# mcu_atmega.net
KiCad netlist of a schematic drawn in Altium Designer
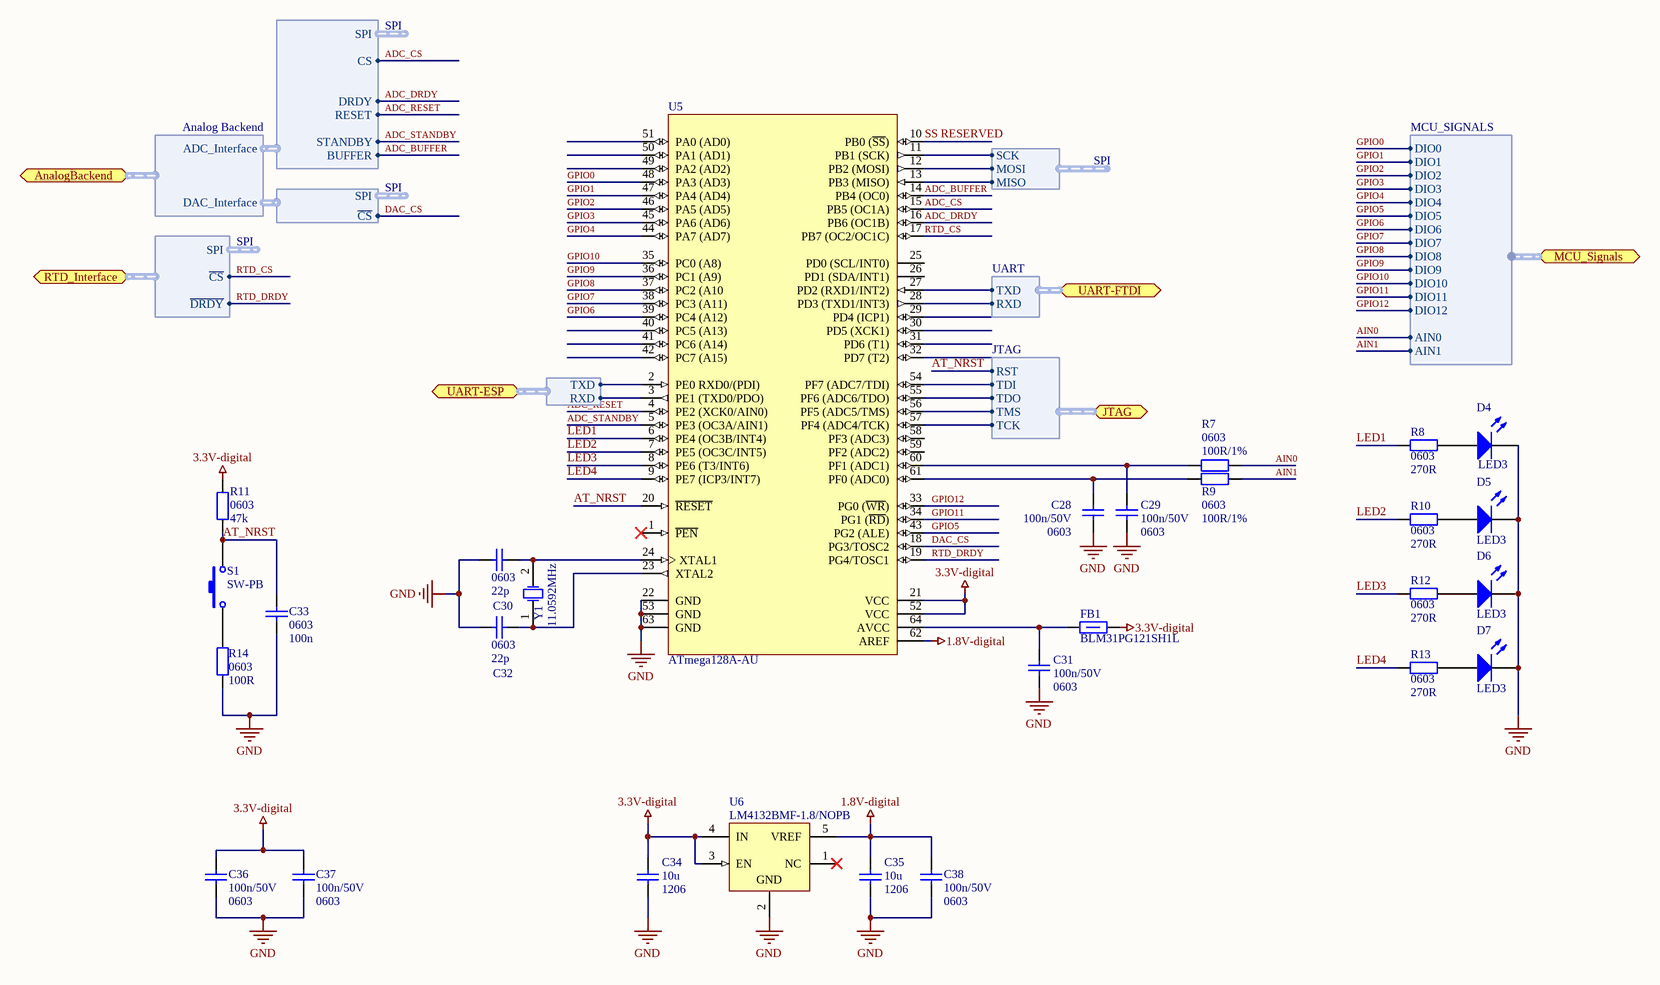
[diagram p0: mcu_atmega.SchDoc]

(export (version "E")
  (design (tool "Eeschema 10.0.6"))
  (components
    (comp (ref "C28")
      (value "100n/50V")
      (footprint "SMD_Capacitor_0603")
      (description "Ceramic Cap Kemet COTS 100n/50V X7R 0603")
      (fields
        (field (name "MANUFACTURER") "Kemet")
        (field (name "MANUFACTURERPARTNUMBER") "C0603T104K5RALTU")
        (field (name "PACKAGE") "0603")
      )
      (libsource (lib "capacitors") (part "Cer_C0603T104K5RALTU"))
    )
    (comp (ref "C29")
      (value "100n/50V")
      (footprint "SMD_Capacitor_0603")
      (description "Ceramic Cap Kemet COTS 100n/50V X7R 0603")
      (fields
        (field (name "MANUFACTURER") "Kemet")
        (field (name "MANUFACTURERPARTNUMBER") "C0603T104K5RALTU")
        (field (name "PACKAGE") "0603")
      )
      (libsource (lib "capacitors") (part "Cer_C0603T104K5RALTU"))
    )
    (comp (ref "C30")
      (value "0603")
      (footprint "SMD_Capacitor_0603")
      (description "Capacitor")
      (fields (field (name "ALTIUM_VALUE") "22p") (field (name "PUBLISHER") "Altium Limited"))
      (libsource (lib "Miscellaneous Devices") (part "Cap"))
    )
    (comp (ref "C31")
      (value "100n/50V")
      (footprint "SMD_Capacitor_0603")
      (description "Ceramic Cap Kemet COTS 100n/50V X7R 0603")
      (fields
        (field (name "MANUFACTURER") "Kemet")
        (field (name "MANUFACTURERPARTNUMBER") "C0603T104K5RALTU")
        (field (name "PACKAGE") "0603")
      )
      (libsource (lib "capacitors") (part "Cer_C0603T104K5RALTU"))
    )
    (comp (ref "C32")
      (value "0603")
      (footprint "SMD_Capacitor_0603")
      (description "Capacitor")
      (fields (field (name "ALTIUM_VALUE") "22p") (field (name "PUBLISHER") "Altium Limited"))
      (libsource (lib "Miscellaneous Devices") (part "Cap"))
    )
    (comp (ref "C33")
      (value "0603")
      (footprint "SMD_Capacitor_0603")
      (description "Capacitor")
      (fields (field (name "ALTIUM_VALUE") "100n") (field (name "PUBLISHER") "Altium Limited"))
      (libsource (lib "Miscellaneous Devices") (part "Cap"))
    )
    (comp (ref "C34")
      (value "10u")
      (footprint "SMD_Capacitor_1206")
      (description "Cap")
      (fields (field (name "PACKAGE") "1206"))
      (libsource (lib "capacitors") (part "Cap"))
    )
    (comp (ref "C35")
      (value "10u")
      (footprint "SMD_Capacitor_1206")
      (description "Cap")
      (fields (field (name "PACKAGE") "1206"))
      (libsource (lib "capacitors") (part "Cap"))
    )
    (comp (ref "C36")
      (value "100n/50V")
      (footprint "SMD_Capacitor_0603")
      (description "Ceramic Cap Kemet COTS 100n/50V X7R 0603")
      (fields
        (field (name "MANUFACTURER") "Kemet")
        (field (name "MANUFACTURERPARTNUMBER") "C0603T104K5RALTU")
        (field (name "PACKAGE") "0603")
      )
      (libsource (lib "capacitors") (part "Cer_C0603T104K5RALTU"))
    )
    (comp (ref "C37")
      (value "100n/50V")
      (footprint "SMD_Capacitor_0603")
      (description "Ceramic Cap Kemet COTS 100n/50V X7R 0603")
      (fields
        (field (name "MANUFACTURER") "Kemet")
        (field (name "MANUFACTURERPARTNUMBER") "C0603T104K5RALTU")
        (field (name "PACKAGE") "0603")
      )
      (libsource (lib "capacitors") (part "Cer_C0603T104K5RALTU"))
    )
    (comp (ref "C38")
      (value "100n/50V")
      (footprint "SMD_Capacitor_0603")
      (description "Ceramic Cap Kemet COTS 100n/50V X7R 0603")
      (fields
        (field (name "MANUFACTURER") "Kemet")
        (field (name "MANUFACTURERPARTNUMBER") "C0603T104K5RALTU")
        (field (name "PACKAGE") "0603")
      )
      (libsource (lib "capacitors") (part "Cer_C0603T104K5RALTU"))
    )
    (comp (ref "D4")
      (value "LED3")
      (footprint "LED 0805 Blue")
      (description "Typical BLUE SiC LED")
      (fields (field (name "PUBLISHER") "Altium Limited"))
      (libsource (lib "Miscellaneous Devices") (part "LED3"))
    )
    (comp (ref "D5")
      (value "LED3")
      (footprint "LED 0805 Yellow")
      (description "Typical BLUE SiC LED")
      (fields (field (name "PUBLISHER") "Altium Limited"))
      (libsource (lib "Miscellaneous Devices") (part "LED3"))
    )
    (comp (ref "D6")
      (value "LED3")
      (footprint "LED 0805 GREEN")
      (description "Typical BLUE SiC LED")
      (fields (field (name "PUBLISHER") "Altium Limited"))
      (libsource (lib "Miscellaneous Devices") (part "LED3"))
    )
    (comp (ref "D7")
      (value "LED3")
      (footprint "LED 0805 RED")
      (description "Typical BLUE SiC LED")
      (fields (field (name "PUBLISHER") "Altium Limited"))
      (libsource (lib "Miscellaneous Devices") (part "LED3"))
    )
    (comp (ref "FB1")
      (value "120R/100MHz")
      (footprint "SMD_FerriteBead_1206")
      (description "Ferrite bead, 1206, 0.02HM, 3.5A.")
      (fields (field (name "MANUFACTURER") "Murata") (field (name "MANUFACTURERPARTNUMBER") "BLM31PG121SH1L"))
      (libsource (lib "inductors") (part "BLM31PG121SH1L"))
    )
    (comp (ref "R7")
      (value "100R/1%")
      (footprint "SMD_Resistor_0603")
      (description "100R/1% Vishay CRCW 0603 Resistor. 100mW, 100ppm, 75V.")
      (fields
        (field (name "MANUFACTURER") "Vishay")
        (field (name "MANUFACTURERPARTNUMBER") "CRCW0603100RFKxxxx")
        (field (name "PACKAGE") "0603")
      )
      (libsource (lib "resistors") (part "CRCW0603100RFKxxxx"))
    )
    (comp (ref "R8")
      (value "0603")
      (footprint "SMD_Resistor_0603")
      (description "Resistor")
      (fields (field (name "ALTIUM_VALUE") "270R") (field (name "PUBLISHER") "Altium Limited"))
      (libsource (lib "Miscellaneous Devices") (part "Res2"))
    )
    (comp (ref "R9")
      (value "100R/1%")
      (footprint "SMD_Resistor_0603")
      (description "100R/1% Vishay CRCW 0603 Resistor. 100mW, 100ppm, 75V.")
      (fields
        (field (name "MANUFACTURER") "Vishay")
        (field (name "MANUFACTURERPARTNUMBER") "CRCW0603100RFKxxxx")
        (field (name "PACKAGE") "0603")
      )
      (libsource (lib "") (part "CRCW0603100RFKxxxx_1"))
    )
    (comp (ref "R10")
      (value "0603")
      (footprint "SMD_Resistor_0603")
      (description "Resistor")
      (fields (field (name "ALTIUM_VALUE") "270R") (field (name "PUBLISHER") "Altium Limited"))
      (libsource (lib "Miscellaneous Devices") (part "Res2"))
    )
    (comp (ref "R11")
      (value "0603")
      (footprint "SMD_Resistor_0603")
      (description "Resistor")
      (fields (field (name "ALTIUM_VALUE") "47k") (field (name "PUBLISHER") "Altium Limited"))
      (libsource (lib "") (part "Res2_2"))
    )
    (comp (ref "R12")
      (value "0603")
      (footprint "SMD_Resistor_0603")
      (description "Resistor")
      (fields (field (name "ALTIUM_VALUE") "270R") (field (name "PUBLISHER") "Altium Limited"))
      (libsource (lib "Miscellaneous Devices") (part "Res2"))
    )
    (comp (ref "R13")
      (value "0603")
      (footprint "SMD_Resistor_0603")
      (description "Resistor")
      (fields (field (name "ALTIUM_VALUE") "270R") (field (name "PUBLISHER") "Altium Limited"))
      (libsource (lib "Miscellaneous Devices") (part "Res2"))
    )
    (comp (ref "R14")
      (value "0603")
      (footprint "SMD_Resistor_0603")
      (description "Resistor")
      (fields (field (name "ALTIUM_VALUE") "100R") (field (name "PUBLISHER") "Altium Limited"))
      (libsource (lib "") (part "Res2_1"))
    )
    (comp (ref "S1")
      (value "SW-PB")
      (footprint "Tact Switch 3x6")
      (description "Switch")
      (fields (field (name "PUBLISHER") "Altium Limited"))
      (libsource (lib "Miscellaneous Devices") (part "SW-PB"))
    )
    (comp (ref "U5")
      (value "ATmega128A-AU")
      (footprint "64A_M")
      (libsource (lib "Atmel Microcontroller megaAVR") (part "ATmega128A-AU"))
    )
    (comp (ref "U6")
      (value "LM4132BMF-1.8/NOPB")
      (footprint "MF05A_N")
      (description "Precision Low Dropout Voltage Reference, 5-pin SOT-23, Pb-Free")
      (fields (field (name "MANUFACTURER") "National Semiconductor"))
      (libsource (lib "National Semiconductor Voltage Reference") (part "LM4132BMF-1.8/NOPB"))
    )
    (comp (ref "Y1")
      (value "11.0592MHz")
      (footprint "CRYSTAL_HC49-US-SM")
      (description "LF XTAL003519")
      (fields (field (name "PUBLISHER") "Altium Limited"))
      (libsource (lib "Miscellaneous Devices") (part "XTAL"))
    )
  )
  (nets
    (net (code "12") (name "/ADC_BUFFER") (class "Default")
      (node (ref "U5") (pin "14") (pinfunction "PB4_(OC0)_14") (pintype "bidirectional"))
    )
    (net (code "13") (name "/ADC_CS") (class "Default")
      (node (ref "U5") (pin "15") (pinfunction "PB5_(OC1A)_15") (pintype "bidirectional"))
    )
    (net (code "14") (name "/ADC_DRDY") (class "Default")
      (node (ref "U5") (pin "16") (pinfunction "PB6_(OC1B)_16") (pintype "bidirectional"))
    )
    (net (code "15") (name "/ADC_RESET") (class "Default")
      (node (ref "U5") (pin "4") (pinfunction "PE2_(XCK0/AIN0)_4") (pintype "bidirectional"))
    )
    (net (code "16") (name "/ADC_STANDBY") (class "Default")
      (node (ref "U5") (pin "5") (pinfunction "PE3_(OC3A/AIN1)_5") (pintype "bidirectional"))
    )
    (net (code "17") (name "/AIN0") (class "Default")
      (node (ref "R7") (pin "1") (pinfunction "1_1") (pintype "passive"))
    )
    (net (code "18") (name "/AIN1") (class "Default")
      (node (ref "R9") (pin "2") (pinfunction "2_2") (pintype "passive"))
    )
    (net (code "19") (name "/AT_NRST") (class "Default")
      (node (ref "C33") (pin "2") (pinfunction "2_2") (pintype "passive"))
      (node (ref "R11") (pin "1") (pinfunction "1_1") (pintype "passive"))
      (node (ref "S1") (pin "2") (pinfunction "2_2") (pintype "passive"))
      (node (ref "U5") (pin "20") (pinfunction "~{RESET}_20") (pintype "input"))
    )
    (net (code "21") (name "/DAC_CS") (class "Default")
      (node (ref "U5") (pin "18") (pinfunction "PG3/TOSC2_18") (pintype "bidirectional"))
    )
    (net (code "22") (name "/GPIO0") (class "Default")
      (node (ref "U5") (pin "48") (pinfunction "PA3_(AD3)_48") (pintype "bidirectional"))
    )
    (net (code "23") (name "/GPIO1") (class "Default")
      (node (ref "U5") (pin "47") (pinfunction "PA4_(AD4)_47") (pintype "bidirectional"))
    )
    (net (code "24") (name "/GPIO2") (class "Default")
      (node (ref "U5") (pin "46") (pinfunction "PA5_(AD5)_46") (pintype "bidirectional"))
    )
    (net (code "25") (name "/GPIO3") (class "Default")
      (node (ref "U5") (pin "45") (pinfunction "PA6_(AD6)_45") (pintype "bidirectional"))
    )
    (net (code "26") (name "/GPIO4") (class "Default")
      (node (ref "U5") (pin "44") (pinfunction "PA7_(AD7)_44") (pintype "bidirectional"))
    )
    (net (code "27") (name "/GPIO5") (class "Default")
      (node (ref "U5") (pin "43") (pinfunction "PG2_(ALE)_43") (pintype "bidirectional"))
    )
    (net (code "28") (name "/GPIO6") (class "Default")
      (node (ref "U5") (pin "39") (pinfunction "PC4_(A12)_39") (pintype "bidirectional"))
    )
    (net (code "29") (name "/GPIO7") (class "Default")
      (node (ref "U5") (pin "38") (pinfunction "PC3_(A11)_38") (pintype "bidirectional"))
    )
    (net (code "30") (name "/GPIO8") (class "Default")
      (node (ref "U5") (pin "37") (pinfunction "PC2_(A10_37") (pintype "bidirectional"))
    )
    (net (code "31") (name "/GPIO9") (class "Default")
      (node (ref "U5") (pin "36") (pinfunction "PC1_(A9)_36") (pintype "bidirectional"))
    )
    (net (code "32") (name "/GPIO10") (class "Default")
      (node (ref "U5") (pin "35") (pinfunction "PC0_(A8)_35") (pintype "bidirectional"))
    )
    (net (code "33") (name "/GPIO11") (class "Default")
      (node (ref "U5") (pin "34") (pinfunction "PG1_(~{RD})_34") (pintype "bidirectional"))
    )
    (net (code "34") (name "/GPIO12") (class "Default")
      (node (ref "U5") (pin "33") (pinfunction "PG0_(~{WR})_33") (pintype "bidirectional"))
    )
    (net (code "35") (name "/LED1") (class "Default")
      (node (ref "R8") (pin "2") (pinfunction "2_2") (pintype "passive"))
      (node (ref "U5") (pin "6") (pinfunction "PE4_(OC3B/INT4)_6") (pintype "bidirectional"))
    )
    (net (code "36") (name "/LED2") (class "Default")
      (node (ref "R10") (pin "2") (pinfunction "2_2") (pintype "passive"))
      (node (ref "U5") (pin "7") (pinfunction "PE5_(OC3C/INT5)_7") (pintype "bidirectional"))
    )
    (net (code "37") (name "/LED3") (class "Default")
      (node (ref "R12") (pin "2") (pinfunction "2_2") (pintype "passive"))
      (node (ref "U5") (pin "8") (pinfunction "PE6_(T3/INT6)_8") (pintype "bidirectional"))
    )
    (net (code "38") (name "/LED4") (class "Default")
      (node (ref "R13") (pin "2") (pinfunction "2_2") (pintype "passive"))
      (node (ref "U5") (pin "9") (pinfunction "PE7_(ICP3/INT7)_9") (pintype "bidirectional"))
    )
    (net (code "39") (name "/MISO") (class "Default")
      (node (ref "U5") (pin "13") (pinfunction "PB3_(MISO)_13") (pintype "input"))
    )
    (net (code "40") (name "/MOSI") (class "Default")
      (node (ref "U5") (pin "12") (pinfunction "PB2_(MOSI)_12") (pintype "output"))
    )
    (net (code "41") (name "/RTD_CS") (class "Default")
      (node (ref "U5") (pin "17") (pinfunction "PB7_(OC2/OC1C)_17") (pintype "bidirectional"))
    )
    (net (code "42") (name "/RTD_DRDY") (class "Default")
      (node (ref "U5") (pin "19") (pinfunction "PG4/TOSC1_19") (pintype "bidirectional"))
    )
    (net (code "43") (name "/SCK") (class "Default")
      (node (ref "U5") (pin "11") (pinfunction "PB1_(SCK)_11") (pintype "output"))
    )
    (net (code "45") (name "/SS RESERVED") (class "Default")
      (node (ref "U5") (pin "10") (pinfunction "PB0_(~{SS})_10") (pintype "bidirectional"))
    )
    (net (code "46") (name "/TCK") (class "Default")
      (node (ref "U5") (pin "57") (pinfunction "PF4_(ADC4/TCK)_57") (pintype "bidirectional"))
    )
    (net (code "47") (name "/TDI") (class "Default")
      (node (ref "U5") (pin "54") (pinfunction "PF7_(ADC7/TDI)_54") (pintype "bidirectional"))
    )
    (net (code "48") (name "/TDO") (class "Default")
      (node (ref "U5") (pin "55") (pinfunction "PF6_(ADC6/TDO)_55") (pintype "bidirectional"))
    )
    (net (code "49") (name "/TMS") (class "Default")
      (node (ref "U5") (pin "56") (pinfunction "PF5_(ADC5/TMS)_56") (pintype "bidirectional"))
    )
    (net (code "57") (name "1.8V-digital") (class "Default")
      (node (ref "C35") (pin "1") (pinfunction "1_1") (pintype "passive"))
      (node (ref "C38") (pin "1") (pinfunction "1_1") (pintype "passive"))
      (node (ref "U5") (pin "62") (pinfunction "AREF_62") (pintype "power_in"))
      (node (ref "U6") (pin "5") (pinfunction "VREF_5") (pintype "power_in"))
    )
    (net (code "58") (name "3.3V-digital") (class "Default")
      (node (ref "C34") (pin "1") (pinfunction "1_1") (pintype "passive"))
      (node (ref "C36") (pin "1") (pinfunction "1_1") (pintype "passive"))
      (node (ref "C37") (pin "1") (pinfunction "1_1") (pintype "passive"))
      (node (ref "FB1") (pin "1") (pinfunction "1_1") (pintype "passive"))
      (node (ref "R11") (pin "2") (pinfunction "2_2") (pintype "passive"))
      (node (ref "U5") (pin "21") (pinfunction "VCC_21") (pintype "power_in"))
      (node (ref "U5") (pin "52") (pinfunction "VCC_52") (pintype "power_in"))
      (node (ref "U6") (pin "3") (pinfunction "EN_3") (pintype "input"))
      (node (ref "U6") (pin "4") (pinfunction "IN_4") (pintype "power_in"))
    )
    (net (code "59") (name "GND") (class "Default")
      (node (ref "C28") (pin "2") (pinfunction "2_2") (pintype "passive"))
      (node (ref "C29") (pin "2") (pinfunction "2_2") (pintype "passive"))
      (node (ref "C30") (pin "1") (pinfunction "1_1") (pintype "passive"))
      (node (ref "C31") (pin "2") (pinfunction "2_2") (pintype "passive"))
      (node (ref "C32") (pin "1") (pinfunction "1_1") (pintype "passive"))
      (node (ref "C33") (pin "1") (pinfunction "1_1") (pintype "passive"))
      (node (ref "C34") (pin "2") (pinfunction "2_2") (pintype "passive"))
      (node (ref "C35") (pin "2") (pinfunction "2_2") (pintype "passive"))
      (node (ref "C36") (pin "2") (pinfunction "2_2") (pintype "passive"))
      (node (ref "C37") (pin "2") (pinfunction "2_2") (pintype "passive"))
      (node (ref "C38") (pin "2") (pinfunction "2_2") (pintype "passive"))
      (node (ref "D4") (pin "2") (pinfunction "K_2") (pintype "passive"))
      (node (ref "D5") (pin "2") (pinfunction "K_2") (pintype "passive"))
      (node (ref "D6") (pin "2") (pinfunction "K_2") (pintype "passive"))
      (node (ref "D7") (pin "2") (pinfunction "K_2") (pintype "passive"))
      (node (ref "R14") (pin "2") (pinfunction "2_2") (pintype "passive"))
      (node (ref "U5") (pin "22") (pinfunction "GND_22") (pintype "power_in"))
      (node (ref "U5") (pin "53") (pinfunction "GND_53") (pintype "power_in"))
      (node (ref "U5") (pin "63") (pinfunction "GND_63") (pintype "power_in"))
      (node (ref "U6") (pin "2") (pinfunction "GND_2") (pintype "power_in"))
    )
    (net (code "60") (name "Net-(D4-A)") (class "Default")
      (node (ref "D4") (pin "1") (pinfunction "A_1") (pintype "passive"))
      (node (ref "R8") (pin "1") (pinfunction "1_1") (pintype "passive"))
    )
    (net (code "61") (name "Net-(D5-A)") (class "Default")
      (node (ref "D5") (pin "1") (pinfunction "A_1") (pintype "passive"))
      (node (ref "R10") (pin "1") (pinfunction "1_1") (pintype "passive"))
    )
    (net (code "62") (name "Net-(D6-A)") (class "Default")
      (node (ref "D6") (pin "1") (pinfunction "A_1") (pintype "passive"))
      (node (ref "R12") (pin "1") (pinfunction "1_1") (pintype "passive"))
    )
    (net (code "63") (name "Net-(D7-A)") (class "Default")
      (node (ref "D7") (pin "1") (pinfunction "A_1") (pintype "passive"))
      (node (ref "R13") (pin "1") (pinfunction "1_1") (pintype "passive"))
    )
    (net (code "64") (name "Net-(R14-Pad1)") (class "Default")
      (node (ref "R14") (pin "1") (pinfunction "1_1") (pintype "passive"))
      (node (ref "S1") (pin "1") (pinfunction "1_1") (pintype "passive"))
    )
    (net (code "65") (name "Net-(U5-AVCC)") (class "Default")
      (node (ref "C31") (pin "1") (pinfunction "1_1") (pintype "passive"))
      (node (ref "FB1") (pin "2") (pinfunction "2_2") (pintype "passive"))
      (node (ref "U5") (pin "64") (pinfunction "AVCC_64") (pintype "power_in"))
    )
    (net (code "66") (name "Net-(U5-PF0_(ADC0))") (class "Default")
      (node (ref "C28") (pin "1") (pinfunction "1_1") (pintype "passive"))
      (node (ref "R9") (pin "1") (pinfunction "1_1") (pintype "passive"))
      (node (ref "U5") (pin "61") (pinfunction "PF0_(ADC0)_61") (pintype "bidirectional"))
    )
    (net (code "67") (name "Net-(U5-PF1_(ADC1))") (class "Default")
      (node (ref "C29") (pin "1") (pinfunction "1_1") (pintype "passive"))
      (node (ref "R7") (pin "2") (pinfunction "2_2") (pintype "passive"))
      (node (ref "U5") (pin "60") (pinfunction "PF1_(ADC1)_60") (pintype "bidirectional"))
    )
    (net (code "68") (name "Net-(U5-XTAL1)") (class "Default")
      (node (ref "C30") (pin "2") (pinfunction "2_2") (pintype "passive"))
      (node (ref "U5") (pin "24") (pinfunction "XTAL1_24") (pintype "input"))
      (node (ref "Y1") (pin "2") (pinfunction "OSC2_2") (pintype "passive"))
    )
    (net (code "69") (name "Net-(U5-XTAL2)") (class "Default")
      (node (ref "C32") (pin "2") (pinfunction "2_2") (pintype "passive"))
      (node (ref "U5") (pin "23") (pinfunction "XTAL2_23") (pintype "output"))
      (node (ref "Y1") (pin "1") (pinfunction "OSC1_1") (pintype "passive"))
    )
    (net (code "70") (name "unconnected-(U5-PA0_(AD0)-Pad51)") (class "Default")
      (node (ref "U5") (pin "51") (pinfunction "PA0_(AD0)_51") (pintype "bidirectional"))
    )
    (net (code "71") (name "unconnected-(U5-PA1_(AD1)-Pad50)") (class "Default")
      (node (ref "U5") (pin "50") (pinfunction "PA1_(AD1)_50") (pintype "bidirectional"))
    )
    (net (code "72") (name "unconnected-(U5-PA2_(AD2)-Pad49)") (class "Default")
      (node (ref "U5") (pin "49") (pinfunction "PA2_(AD2)_49") (pintype "bidirectional"))
    )
    (net (code "73") (name "unconnected-(U5-PC5_(A13)-Pad40)") (class "Default")
      (node (ref "U5") (pin "40") (pinfunction "PC5_(A13)_40") (pintype "bidirectional"))
    )
    (net (code "74") (name "unconnected-(U5-PC6_(A14)-Pad41)") (class "Default")
      (node (ref "U5") (pin "41") (pinfunction "PC6_(A14)_41") (pintype "bidirectional"))
    )
    (net (code "75") (name "unconnected-(U5-PC7_(A15)-Pad42)") (class "Default")
      (node (ref "U5") (pin "42") (pinfunction "PC7_(A15)_42") (pintype "bidirectional"))
    )
    (net (code "76") (name "unconnected-(U5-PD0_(SCL{slash}INT0)-Pad25)") (class "Default")
      (node (ref "U5") (pin "25") (pinfunction "PD0_(SCL/INT0)_25") (pintype "open_collector"))
    )
    (net (code "77") (name "unconnected-(U5-PD1_(SDA{slash}INT1)-Pad26)") (class "Default")
      (node (ref "U5") (pin "26") (pinfunction "PD1_(SDA/INT1)_26") (pintype "open_collector"))
    )
    (net (code "78") (name "unconnected-(U5-PD2_(RXD1{slash}INT2)-Pad27)") (class "Default")
      (node (ref "U5") (pin "27") (pinfunction "PD2_(RXD1/INT2)_27") (pintype "input"))
    )
    (net (code "79") (name "unconnected-(U5-PD3_(TXD1{slash}INT3)-Pad28)") (class "Default")
      (node (ref "U5") (pin "28") (pinfunction "PD3_(TXD1/INT3)_28") (pintype "output"))
    )
    (net (code "80") (name "unconnected-(U5-PD4_(ICP1)-Pad29)") (class "Default")
      (node (ref "U5") (pin "29") (pinfunction "PD4_(ICP1)_29") (pintype "bidirectional"))
    )
    (net (code "81") (name "unconnected-(U5-PD5_(XCK1)-Pad30)") (class "Default")
      (node (ref "U5") (pin "30") (pinfunction "PD5_(XCK1)_30") (pintype "bidirectional"))
    )
    (net (code "82") (name "unconnected-(U5-PD6_(T1)-Pad31)") (class "Default")
      (node (ref "U5") (pin "31") (pinfunction "PD6_(T1)_31") (pintype "bidirectional"))
    )
    (net (code "83") (name "unconnected-(U5-PD7_(T2)-Pad32)") (class "Default")
      (node (ref "U5") (pin "32") (pinfunction "PD7_(T2)_32") (pintype "bidirectional"))
    )
    (net (code "84") (name "unconnected-(U5-PE0_RXD0{slash}(PDI)-Pad2)") (class "Default")
      (node (ref "U5") (pin "2") (pinfunction "PE0_RXD0/(PDI)_2") (pintype "input"))
    )
    (net (code "85") (name "unconnected-(U5-PE1_(TXD0{slash}PDO)-Pad3)") (class "Default")
      (node (ref "U5") (pin "3") (pinfunction "PE1_(TXD0/PDO)_3") (pintype "output"))
    )
    (net (code "86") (name "unconnected-(U5-PF2_(ADC2)-Pad59)") (class "Default")
      (node (ref "U5") (pin "59") (pinfunction "PF2_(ADC2)_59") (pintype "bidirectional"))
    )
    (net (code "87") (name "unconnected-(U5-PF3_(ADC3)-Pad58)") (class "Default")
      (node (ref "U5") (pin "58") (pinfunction "PF3_(ADC3)_58") (pintype "bidirectional"))
    )
    (net (code "88") (name "unconnected-(U5-~{PEN}-Pad1)") (class "Default")
      (node (ref "U5") (pin "1") (pinfunction "~{PEN}_1") (pintype "input+no_connect"))
    )
    (net (code "89") (name "unconnected-(U6-NC-Pad1)") (class "Default")
      (node (ref "U6") (pin "1") (pinfunction "NC_1") (pintype "passive+no_connect"))
    )
  )
)
